# EAA690_RFID.net
KiCad netlist of a schematic drawn in EAGLE
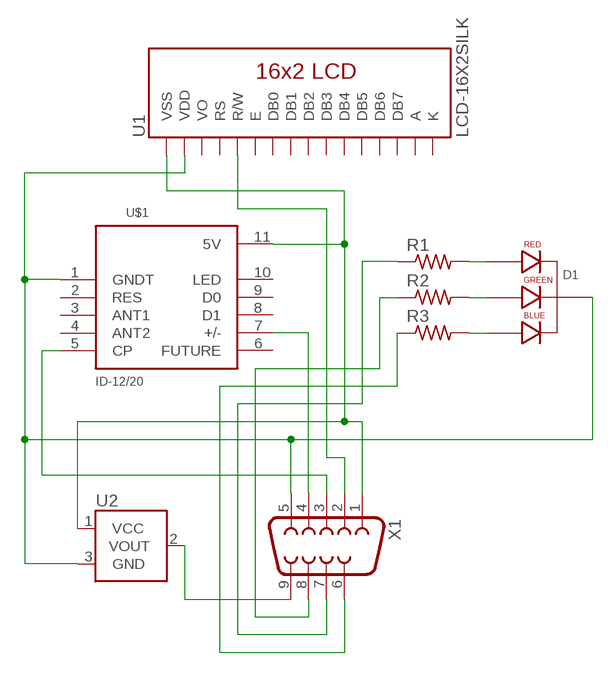
[diagram p0: schematic, sheet 1]

(export (version "E")
  (design (tool "Eeschema 10.0.6"))
  (components
    (comp (ref "D1")
      (value "LED-RGB-CC-THRUDIFFUSE")
      (footprint "eagle-import:LED-RGB-THRU")
      (libsource (lib "eagle-import") (part "LED-RGB-CC-THRUDIFFUSE"))
    )
    (comp (ref "R1")
      (value "R-US_0204/7")
      (footprint "eagle-import:0204_7")
      (libsource (lib "eagle-import") (part "R-US_0204/7"))
    )
    (comp (ref "R2")
      (value "R-US_0204/7")
      (footprint "eagle-import:0204_7")
      (libsource (lib "eagle-import") (part "R-US_0204/7"))
    )
    (comp (ref "R3")
      (value "R-US_0204/7")
      (footprint "eagle-import:0204_7")
      (libsource (lib "eagle-import") (part "R-US_0204/7"))
    )
    (comp (ref "U$1")
      (value "ID-12/20")
      (footprint "eagle-import:ID-12")
      (libsource (lib "eagle-import") (part "ID-12/20"))
    )
    (comp (ref "U1")
      (value "LCD-16X2SILK")
      (footprint "eagle-import:LCD-16X2")
      (libsource (lib "eagle-import") (part "LCD-16X2SILK"))
    )
    (comp (ref "U2")
      (value "TMP36GT9")
      (footprint "eagle-import:TO-92")
      (libsource (lib "eagle-import") (part "TMP36GT9"))
    )
    (comp (ref "X1")
      (value "DB9FEMALE")
      (footprint "eagle-import:DB9")
      (libsource (lib "eagle-import") (part "DB9FEMALE"))
    )
  )
  (nets
    (net (code "1") (name "/A") (class "Default")
      (node (ref "U1") (pin "15") (pinfunction "A_15") (pintype "power_in"))
    )
    (net (code "2") (name "/K") (class "Default")
      (node (ref "U1") (pin "16") (pinfunction "K_16") (pintype "power_in"))
    )
    (net (code "3") (name "Net-(D1-BLUE_CATHODE)") (class "Default")
      (node (ref "D1") (pin "4") (pinfunction "BLUE_CATHODE_4") (pintype "bidirectional"))
      (node (ref "R3") (pin "2") (pinfunction "2_2") (pintype "passive"))
    )
    (net (code "4") (name "Net-(D1-CATHODE)") (class "Default")
      (node (ref "D1") (pin "2") (pinfunction "CATHODE_2") (pintype "bidirectional"))
      (node (ref "U$1") (pin "1") (pinfunction "GNDT_1") (pintype "bidirectional"))
      (node (ref "U1") (pin "2") (pinfunction "VDD_2") (pintype "power_in"))
      (node (ref "U2") (pin "3") (pinfunction "GND_3") (pintype "bidirectional"))
      (node (ref "X1") (pin "5") (pinfunction "5_5") (pintype "passive"))
    )
    (net (code "5") (name "Net-(D1-GREEN_CATHODE)") (class "Default")
      (node (ref "D1") (pin "3") (pinfunction "GREEN_CATHODE_3") (pintype "bidirectional"))
      (node (ref "R2") (pin "2") (pinfunction "2_2") (pintype "passive"))
    )
    (net (code "6") (name "Net-(D1-RED_CATHODE)") (class "Default")
      (node (ref "D1") (pin "1") (pinfunction "RED_CATHODE_1") (pintype "bidirectional"))
      (node (ref "R1") (pin "2") (pinfunction "2_2") (pintype "passive"))
    )
    (net (code "7") (name "Net-(R1-Pad1)") (class "Default")
      (node (ref "R1") (pin "1") (pinfunction "1_1") (pintype "passive"))
      (node (ref "X1") (pin "7") (pinfunction "7_7") (pintype "passive"))
    )
    (net (code "8") (name "Net-(R2-Pad1)") (class "Default")
      (node (ref "R2") (pin "1") (pinfunction "1_1") (pintype "passive"))
      (node (ref "X1") (pin "8") (pinfunction "8_8") (pintype "passive"))
    )
    (net (code "9") (name "Net-(R3-Pad1)") (class "Default")
      (node (ref "R3") (pin "1") (pinfunction "1_1") (pintype "passive"))
      (node (ref "X1") (pin "6") (pinfunction "6_6") (pintype "passive"))
    )
    (net (code "10") (name "Net-(U$1-+{slash}-)") (class "Default")
      (node (ref "U$1") (pin "7") (pinfunction "+/-_7") (pintype "bidirectional"))
      (node (ref "X1") (pin "4") (pinfunction "4_4") (pintype "passive"))
    )
    (net (code "11") (name "Net-(U$1-5V)") (class "Default")
      (node (ref "U$1") (pin "11") (pinfunction "5V_11") (pintype "bidirectional"))
      (node (ref "U1") (pin "1") (pinfunction "VSS_1") (pintype "power_in"))
      (node (ref "U2") (pin "1") (pinfunction "VCC_1") (pintype "bidirectional"))
      (node (ref "X1") (pin "1") (pinfunction "1_1") (pintype "passive"))
    )
    (net (code "12") (name "Net-(U$1-CP)") (class "Default")
      (node (ref "U$1") (pin "5") (pinfunction "CP_5") (pintype "bidirectional"))
      (node (ref "X1") (pin "3") (pinfunction "3_3") (pintype "passive"))
    )
    (net (code "13") (name "Net-(U1-R{slash}W)") (class "Default")
      (node (ref "U1") (pin "5") (pinfunction "R/W_5") (pintype "input"))
      (node (ref "X1") (pin "2") (pinfunction "2_2") (pintype "passive"))
    )
    (net (code "14") (name "Net-(U2-VOUT)") (class "Default")
      (node (ref "U2") (pin "2") (pinfunction "VOUT_2") (pintype "bidirectional"))
      (node (ref "X1") (pin "9") (pinfunction "9_9") (pintype "passive"))
    )
    (net (code "15") (name "unconnected-(U$1-ANT1-Pad3)") (class "Default")
      (node (ref "U$1") (pin "3") (pinfunction "ANT1_3") (pintype "bidirectional"))
    )
    (net (code "16") (name "unconnected-(U$1-ANT2-Pad4)") (class "Default")
      (node (ref "U$1") (pin "4") (pinfunction "ANT2_4") (pintype "bidirectional"))
    )
    (net (code "17") (name "unconnected-(U$1-D0-Pad9)") (class "Default")
      (node (ref "U$1") (pin "9") (pinfunction "D0_9") (pintype "bidirectional"))
    )
    (net (code "18") (name "unconnected-(U$1-D1-Pad8)") (class "Default")
      (node (ref "U$1") (pin "8") (pinfunction "D1_8") (pintype "bidirectional"))
    )
    (net (code "19") (name "unconnected-(U$1-FUTURE-Pad6)") (class "Default")
      (node (ref "U$1") (pin "6") (pinfunction "FUTURE_6") (pintype "bidirectional"))
    )
    (net (code "20") (name "unconnected-(U$1-LED-Pad10)") (class "Default")
      (node (ref "U$1") (pin "10") (pinfunction "LED_10") (pintype "bidirectional"))
    )
    (net (code "21") (name "unconnected-(U$1-RES-Pad2)") (class "Default")
      (node (ref "U$1") (pin "2") (pinfunction "RES_2") (pintype "bidirectional"))
    )
    (net (code "22") (name "unconnected-(U1-DB0-Pad7)") (class "Default")
      (node (ref "U1") (pin "7") (pinfunction "DB0_7") (pintype "bidirectional"))
    )
    (net (code "23") (name "unconnected-(U1-DB1-Pad8)") (class "Default")
      (node (ref "U1") (pin "8") (pinfunction "DB1_8") (pintype "bidirectional"))
    )
    (net (code "24") (name "unconnected-(U1-DB2-Pad9)") (class "Default")
      (node (ref "U1") (pin "9") (pinfunction "DB2_9") (pintype "bidirectional"))
    )
    (net (code "25") (name "unconnected-(U1-DB3-Pad10)") (class "Default")
      (node (ref "U1") (pin "10") (pinfunction "DB3_10") (pintype "bidirectional"))
    )
    (net (code "26") (name "unconnected-(U1-DB4-Pad11)") (class "Default")
      (node (ref "U1") (pin "11") (pinfunction "DB4_11") (pintype "bidirectional"))
    )
    (net (code "27") (name "unconnected-(U1-DB5-Pad12)") (class "Default")
      (node (ref "U1") (pin "12") (pinfunction "DB5_12") (pintype "bidirectional"))
    )
    (net (code "28") (name "unconnected-(U1-DB6-Pad13)") (class "Default")
      (node (ref "U1") (pin "13") (pinfunction "DB6_13") (pintype "bidirectional"))
    )
    (net (code "29") (name "unconnected-(U1-DB7-Pad14)") (class "Default")
      (node (ref "U1") (pin "14") (pinfunction "DB7_14") (pintype "bidirectional"))
    )
    (net (code "30") (name "unconnected-(U1-E-Pad6)") (class "Default")
      (node (ref "U1") (pin "6") (pinfunction "E_6") (pintype "input"))
    )
    (net (code "31") (name "unconnected-(U1-RS-Pad4)") (class "Default")
      (node (ref "U1") (pin "4") (pinfunction "RS_4") (pintype "input"))
    )
    (net (code "32") (name "unconnected-(U1-VO-Pad3)") (class "Default")
      (node (ref "U1") (pin "3") (pinfunction "VO_3") (pintype "bidirectional"))
    )
  )
)
